# Sheet3_MCU_PSU.net
KiCad netlist of a schematic drawn in Altium Designer
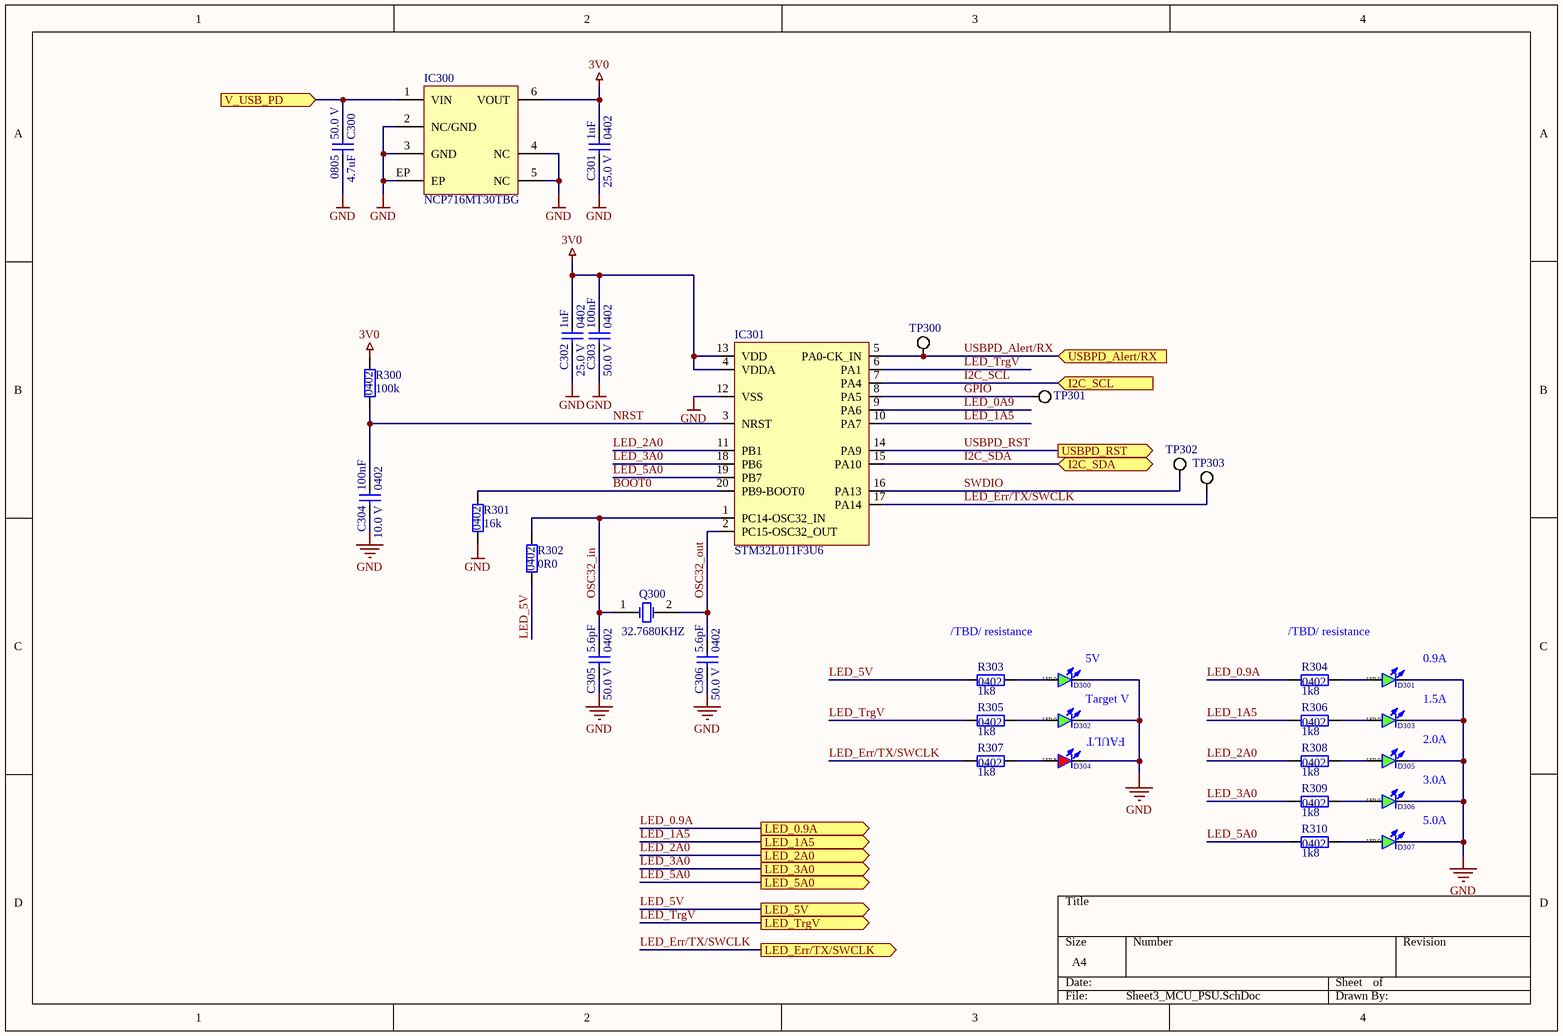
[diagram p0: Sheet3_MCU_PSU.SchDoc]

(export (version "E")
  (design (tool "Eeschema 10.0.6"))
  (components
    (comp (ref "C300")
      (value "C 4.7uF 0805 50V")
      (footprint "0805")
      (description "CAP CER 4.7UF 50V X5R 0805")
      (fields
        (field (name "MANUFACTURER") "Samsung Electro-Mechanics")
        (field (name "MANUFACTURER PART NUMBER") "CL21A475KBQNNNE")
        (field (name "CAPACITANCE") "4.7uF")
        (field (name "VOLTAGE") "50.0 V")
      )
      (libsource (lib "CS_Part_Library") (part "CAP_4.7uF_50V_0805"))
    )
    (comp (ref "C301")
      (value "C 1uF 0402 25V")
      (footprint "0402")
      (description "CAP CER 1UF 25V X5R 0402")
      (fields
        (field (name "MANUFACTURER") "Taiyo Yuden")
        (field (name "MANUFACTURER PART NUMBER") "TMK105BJ105MV-F")
        (field (name "CAPACITANCE") "1uF")
        (field (name "VOLTAGE") "25.0 V")
      )
      (libsource (lib "CS_Part_Library") (part "CAP_1uF_25V_0402"))
    )
    (comp (ref "C302")
      (value "C 1uF 0402 25V")
      (footprint "0402")
      (description "CAP CER 1UF 25V X5R 0402")
      (fields
        (field (name "MANUFACTURER") "Taiyo Yuden")
        (field (name "MANUFACTURER PART NUMBER") "TMK105BJ105MV-F")
        (field (name "CAPACITANCE") "1uF")
        (field (name "VOLTAGE") "25.0 V")
      )
      (libsource (lib "CS_Part_Library") (part "CAP_1uF_25V_0402"))
    )
    (comp (ref "C303")
      (value "C 100nF 0402 50V")
      (footprint "0402")
      (description "CAP CER 0.1UF 50V X7R 0402")
      (fields
        (field (name "MANUFACTURER") "Murata Electronics")
        (field (name "MANUFACTURER PART NUMBER") "GRM155R71H104KE14J")
        (field (name "CAPACITANCE") "100nF")
        (field (name "VOLTAGE") "50.0 V")
      )
      (libsource (lib "CS_Part_Library") (part "CAP_100nF_50V_0402"))
    )
    (comp (ref "C304")
      (value "C 100nF 0402 10V")
      (footprint "0402")
      (description "CAP CER 0.1UF 10V X5R 0402")
      (fields
        (field (name "MANUFACTURER") "Samsung Electro-Mechanics")
        (field (name "MANUFACTURER PART NUMBER") "CL05A104MP5NNNC")
        (field (name "CAPACITANCE") "100nF")
        (field (name "VOLTAGE") "10.0 V")
      )
      (libsource (lib "CS_Part_Library") (part "CAP_100nF_10V_0402"))
    )
    (comp (ref "C305")
      (value "C 5.6pF 0402 50V")
      (footprint "0402")
      (description "CAP CER 5.6PF 50V C0G/NP0 0402")
      (fields
        (field (name "MANUFACTURER") "Samsung Electro-Mechanics")
        (field (name "MANUFACTURER PART NUMBER") "CL05C5R6DB5NNNC")
        (field (name "CAPACITANCE") "5.6pF")
        (field (name "VOLTAGE") "50.0 V")
      )
      (libsource (lib "CS_Part_Library") (part "CAP_5.6PF_50V_0402"))
    )
    (comp (ref "C306")
      (value "C 5.6pF 0402 50V")
      (footprint "0402")
      (description "CAP CER 5.6PF 50V C0G/NP0 0402")
      (fields
        (field (name "MANUFACTURER") "Samsung Electro-Mechanics")
        (field (name "MANUFACTURER PART NUMBER") "CL05C5R6DB5NNNC")
        (field (name "CAPACITANCE") "5.6pF")
        (field (name "VOLTAGE") "50.0 V")
      )
      (libsource (lib "CS_Part_Library") (part "CAP_5.6PF_50V_0402"))
    )
    (comp (ref "D300")
      (value "LED G")
      (footprint "LED_0603")
      (description "LED GREEN DIFFUSED 0603 SMD")
      (fields
        (field (name "MANUFACTURER") "OSRAM Opto Semiconductors Inc.")
        (field (name "MANUFACTURER PART NUMBER") "LT Q39G-Q1OO-25-1")
      )
      (libsource (lib "CS_Part_Library") (part "D_LED_Green_0603"))
    )
    (comp (ref "D301")
      (value "LED G")
      (footprint "LED_0603")
      (description "LED GREEN DIFFUSED 0603 SMD")
      (fields
        (field (name "MANUFACTURER") "OSRAM Opto Semiconductors Inc.")
        (field (name "MANUFACTURER PART NUMBER") "LT Q39G-Q1OO-25-1")
      )
      (libsource (lib "CS_Part_Library") (part "D_LED_Green_0603"))
    )
    (comp (ref "D302")
      (value "LED G")
      (footprint "LED_0603")
      (description "LED GREEN DIFFUSED 0603 SMD")
      (fields
        (field (name "MANUFACTURER") "OSRAM Opto Semiconductors Inc.")
        (field (name "MANUFACTURER PART NUMBER") "LT Q39G-Q1OO-25-1")
      )
      (libsource (lib "CS_Part_Library") (part "D_LED_Green_0603"))
    )
    (comp (ref "D303")
      (value "LED G")
      (footprint "LED_0603")
      (description "LED GREEN DIFFUSED 0603 SMD")
      (fields
        (field (name "MANUFACTURER") "OSRAM Opto Semiconductors Inc.")
        (field (name "MANUFACTURER PART NUMBER") "LT Q39G-Q1OO-25-1")
      )
      (libsource (lib "CS_Part_Library") (part "D_LED_Green_0603"))
    )
    (comp (ref "D304")
      (value "LED R")
      (footprint "LED_0603")
      (description "LED RED DIFFUSED 0603 SMD")
      (fields
        (field (name "MANUFACTURER") "OSRAM Opto Semiconductors Inc.")
        (field (name "MANUFACTURER PART NUMBER") "LS Q976-NR-1")
      )
      (libsource (lib "CS_Part_Library") (part "D_LED_Red_0603"))
    )
    (comp (ref "D305")
      (value "LED G")
      (footprint "LED_0603")
      (description "LED GREEN DIFFUSED 0603 SMD")
      (fields
        (field (name "MANUFACTURER") "OSRAM Opto Semiconductors Inc.")
        (field (name "MANUFACTURER PART NUMBER") "LT Q39G-Q1OO-25-1")
      )
      (libsource (lib "CS_Part_Library") (part "D_LED_Green_0603"))
    )
    (comp (ref "D306")
      (value "LED G")
      (footprint "LED_0603")
      (description "LED GREEN DIFFUSED 0603 SMD")
      (fields
        (field (name "MANUFACTURER") "OSRAM Opto Semiconductors Inc.")
        (field (name "MANUFACTURER PART NUMBER") "LT Q39G-Q1OO-25-1")
      )
      (libsource (lib "CS_Part_Library") (part "D_LED_Green_0603"))
    )
    (comp (ref "D307")
      (value "LED G")
      (footprint "LED_0603")
      (description "LED GREEN DIFFUSED 0603 SMD")
      (fields
        (field (name "MANUFACTURER") "OSRAM Opto Semiconductors Inc.")
        (field (name "MANUFACTURER PART NUMBER") "LT Q39G-Q1OO-25-1")
      )
      (libsource (lib "CS_Part_Library") (part "D_LED_Green_0603"))
    )
    (comp (ref "IC300")
      (value "NCP716MT30TBG")
      (footprint "WDFN-6_EP")
      (description "IC REG LINEAR 3V 80MA 6WDFN")
      (fields (field (name "MANUFACTURER") "onsemi"))
      (libsource (lib "CS_Part_Library") (part "IC_Reg_NCP716MT30TBG"))
    )
    (comp (ref "IC301")
      (value "STM32L011F3U6")
      (footprint "UFQFN-20")
      (description "IC MCU 32BIT 8KB FLASH 20UFQFPN")
      (fields
        (field (name "MANUFACTURER") "STMicroelectronics")
        (field (name "MANUFACTURER PART NUMBER") "STM32L011F3U6TR")
      )
      (libsource (lib "CS_Part_Library") (part "IC_MCU_STM32L011F3U6"))
    )
    (comp (ref "Q300")
      (value "32.7680KHZ")
      (footprint "Q2_3.2x1.5")
      (description "CRYSTAL 32.7680KHZ 12.5PF SMD")
      (fields
        (field (name "MANUFACTURER") "NDK America, Inc.")
        (field (name "MANUFACTURER PART NUMBER") "NX3215SA-32.768K-EXS00A-MU00003")
      )
      (libsource (lib "CS_Part_Library") (part "Q_32k768_12p5"))
    )
    (comp (ref "R300")
      (value "R 100k 0402")
      (footprint "0402")
      (description "RES 100K OHM 5% 1/16W 0402")
      (fields
        (field (name "MANUFACTURER") "YAGEO")
        (field (name "MANUFACTURER PART NUMBER") "RC0402JR-07100KL")
        (field (name "RESISTANCE") "100k")
      )
      (libsource (lib "CS_Part_Library") (part "R_100k_0402"))
    )
    (comp (ref "R301")
      (value "R 16k 0402")
      (footprint "0402")
      (description "RES 16K OHM 1% 1/16W 0402")
      (fields
        (field (name "MANUFACTURER") "Stackpole Electronics Inc")
        (field (name "MANUFACTURER PART NUMBER") "RMCF0402FT16K0")
        (field (name "RESISTANCE") "16k")
      )
      (libsource (lib "CS_Part_Library") (part "R_16k_0402"))
    )
    (comp (ref "R302")
      (value "R 0R0 0402")
      (footprint "0402")
      (description "RES 0 OHM JUMPER 1/16W 0402")
      (fields
        (field (name "MANUFACTURER") "Stackpole Electronics Inc")
        (field (name "MANUFACTURER PART NUMBER") "RMCF0402ZT0R00")
        (field (name "RESISTANCE") "0R0")
      )
      (libsource (lib "CS_Part_Library") (part "R_0R0_0402"))
    )
    (comp (ref "R303")
      (value "R 1k8 0402")
      (footprint "0402")
      (description "RES 1.8K OHM 1% 1/16W 0402")
      (fields
        (field (name "MANUFACTURER") "Stackpole Electronics Inc")
        (field (name "MANUFACTURER PART NUMBER") "RMCF0402FT1K80")
        (field (name "RESISTANCE") "1k8")
      )
      (libsource (lib "CS_Part_Library") (part "R_1k8_0402"))
    )
    (comp (ref "R304")
      (value "R 1k8 0402")
      (footprint "0402")
      (description "RES 1.8K OHM 1% 1/16W 0402")
      (fields
        (field (name "MANUFACTURER") "Stackpole Electronics Inc")
        (field (name "MANUFACTURER PART NUMBER") "RMCF0402FT1K80")
        (field (name "RESISTANCE") "1k8")
      )
      (libsource (lib "CS_Part_Library") (part "R_1k8_0402"))
    )
    (comp (ref "R305")
      (value "R 1k8 0402")
      (footprint "0402")
      (description "RES 1.8K OHM 1% 1/16W 0402")
      (fields
        (field (name "MANUFACTURER") "Stackpole Electronics Inc")
        (field (name "MANUFACTURER PART NUMBER") "RMCF0402FT1K80")
        (field (name "RESISTANCE") "1k8")
      )
      (libsource (lib "CS_Part_Library") (part "R_1k8_0402"))
    )
    (comp (ref "R306")
      (value "R 1k8 0402")
      (footprint "0402")
      (description "RES 1.8K OHM 1% 1/16W 0402")
      (fields
        (field (name "MANUFACTURER") "Stackpole Electronics Inc")
        (field (name "MANUFACTURER PART NUMBER") "RMCF0402FT1K80")
        (field (name "RESISTANCE") "1k8")
      )
      (libsource (lib "CS_Part_Library") (part "R_1k8_0402"))
    )
    (comp (ref "R307")
      (value "R 1k8 0402")
      (footprint "0402")
      (description "RES 1.8K OHM 1% 1/16W 0402")
      (fields
        (field (name "MANUFACTURER") "Stackpole Electronics Inc")
        (field (name "MANUFACTURER PART NUMBER") "RMCF0402FT1K80")
        (field (name "RESISTANCE") "1k8")
      )
      (libsource (lib "CS_Part_Library") (part "R_1k8_0402"))
    )
    (comp (ref "R308")
      (value "R 1k8 0402")
      (footprint "0402")
      (description "RES 1.8K OHM 1% 1/16W 0402")
      (fields
        (field (name "MANUFACTURER") "Stackpole Electronics Inc")
        (field (name "MANUFACTURER PART NUMBER") "RMCF0402FT1K80")
        (field (name "RESISTANCE") "1k8")
      )
      (libsource (lib "CS_Part_Library") (part "R_1k8_0402"))
    )
    (comp (ref "R309")
      (value "R 1k8 0402")
      (footprint "0402")
      (description "RES 1.8K OHM 1% 1/16W 0402")
      (fields
        (field (name "MANUFACTURER") "Stackpole Electronics Inc")
        (field (name "MANUFACTURER PART NUMBER") "RMCF0402FT1K80")
        (field (name "RESISTANCE") "1k8")
      )
      (libsource (lib "CS_Part_Library") (part "R_1k8_0402"))
    )
    (comp (ref "R310")
      (value "R 1k8 0402")
      (footprint "0402")
      (description "RES 1.8K OHM 1% 1/16W 0402")
      (fields
        (field (name "MANUFACTURER") "Stackpole Electronics Inc")
        (field (name "MANUFACTURER PART NUMBER") "RMCF0402FT1K80")
        (field (name "RESISTANCE") "1k8")
      )
      (libsource (lib "CS_Part_Library") (part "R_1k8_0402"))
    )
    (comp (ref "TP300")
      (value "TP")
      (footprint "TP_1mm")
      (description "Test Point 1mm")
      (libsource (lib "CS_Part_Library") (part "TP_1mm"))
    )
    (comp (ref "TP301")
      (value "TP")
      (footprint "TP_1mm")
      (description "Test Point 1mm")
      (libsource (lib "CS_Part_Library") (part "TP_1mm"))
    )
    (comp (ref "TP302")
      (value "TP")
      (footprint "TP_1mm")
      (description "Test Point 1mm")
      (libsource (lib "CS_Part_Library") (part "TP_1mm"))
    )
    (comp (ref "TP303")
      (value "TP")
      (footprint "TP_1mm")
      (description "Test Point 1mm")
      (libsource (lib "CS_Part_Library") (part "TP_1mm"))
    )
  )
  (nets
    (net (code "1") (name "/BOOT0") (class "Default")
      (node (ref "IC301") (pin "20") (pinfunction "PB9-BOOT0_20") (pintype "passive"))
      (node (ref "R301") (pin "2") (pinfunction "2_2") (pintype "passive"))
    )
    (net (code "2") (name "/GPIO") (class "Default")
      (node (ref "IC301") (pin "8") (pinfunction "PA5_8") (pintype "passive"))
      (node (ref "TP301") (pin "1") (pinfunction "TP_1") (pintype "passive"))
    )
    (net (code "3") (name "/I2C_SCL") (class "Default")
      (node (ref "IC301") (pin "7") (pinfunction "PA4_7") (pintype "passive"))
    )
    (net (code "4") (name "/I2C_SDA") (class "Default")
      (node (ref "IC301") (pin "15") (pinfunction "PA10_15") (pintype "passive"))
    )
    (net (code "5") (name "/LED_0.9A") (class "Default")
      (node (ref "R304") (pin "2") (pinfunction "2_2") (pintype "passive"))
    )
    (net (code "6") (name "/LED_0A9") (class "Default")
      (node (ref "IC301") (pin "9") (pinfunction "PA6_9") (pintype "passive"))
    )
    (net (code "7") (name "/LED_1A5") (class "Default")
      (node (ref "IC301") (pin "10") (pinfunction "PA7_10") (pintype "passive"))
      (node (ref "R306") (pin "2") (pinfunction "2_2") (pintype "passive"))
    )
    (net (code "8") (name "/LED_2A0") (class "Default")
      (node (ref "IC301") (pin "11") (pinfunction "PB1_11") (pintype "passive"))
      (node (ref "R308") (pin "2") (pinfunction "2_2") (pintype "passive"))
    )
    (net (code "9") (name "/LED_3A0") (class "Default")
      (node (ref "IC301") (pin "18") (pinfunction "PB6_18") (pintype "passive"))
      (node (ref "R309") (pin "2") (pinfunction "2_2") (pintype "passive"))
    )
    (net (code "10") (name "/LED_5A0") (class "Default")
      (node (ref "IC301") (pin "19") (pinfunction "PB7_19") (pintype "passive"))
      (node (ref "R310") (pin "2") (pinfunction "2_2") (pintype "passive"))
    )
    (net (code "11") (name "/LED_5V") (class "Default")
      (node (ref "R302") (pin "1") (pinfunction "1_1") (pintype "passive"))
      (node (ref "R303") (pin "2") (pinfunction "2_2") (pintype "passive"))
    )
    (net (code "12") (name "/LED_Err{slash}TX{slash}SWCLK") (class "Default")
      (node (ref "IC301") (pin "17") (pinfunction "PA14_17") (pintype "passive"))
      (node (ref "R307") (pin "2") (pinfunction "2_2") (pintype "passive"))
      (node (ref "TP303") (pin "1") (pinfunction "TP_1") (pintype "passive"))
    )
    (net (code "13") (name "/LED_TrgV") (class "Default")
      (node (ref "IC301") (pin "6") (pinfunction "PA1_6") (pintype "passive"))
      (node (ref "R305") (pin "2") (pinfunction "2_2") (pintype "passive"))
    )
    (net (code "14") (name "/NRST") (class "Default")
      (node (ref "C304") (pin "2") (pinfunction "2_2") (pintype "passive"))
      (node (ref "IC301") (pin "3") (pinfunction "NRST_3") (pintype "passive"))
      (node (ref "R300") (pin "1") (pinfunction "1_1") (pintype "passive"))
    )
    (net (code "15") (name "/OSC32_in") (class "Default")
      (node (ref "C305") (pin "2") (pinfunction "2_2") (pintype "passive"))
      (node (ref "IC301") (pin "1") (pinfunction "PC14-OSC32_IN_1") (pintype "passive"))
      (node (ref "Q300") (pin "1") (pinfunction "OSC1_1") (pintype "passive"))
      (node (ref "R302") (pin "2") (pinfunction "2_2") (pintype "passive"))
    )
    (net (code "16") (name "/OSC32_out") (class "Default")
      (node (ref "C306") (pin "2") (pinfunction "2_2") (pintype "passive"))
      (node (ref "IC301") (pin "2") (pinfunction "PC15-OSC32_OUT_2") (pintype "passive"))
      (node (ref "Q300") (pin "2") (pinfunction "OSC2_2") (pintype "passive"))
    )
    (net (code "17") (name "/SWDIO") (class "Default")
      (node (ref "IC301") (pin "16") (pinfunction "PA13_16") (pintype "passive"))
      (node (ref "TP302") (pin "1") (pinfunction "TP_1") (pintype "passive"))
    )
    (net (code "18") (name "/USBPD_Alert{slash}RX") (class "Default")
      (node (ref "IC301") (pin "5") (pinfunction "PA0-CK_IN_5") (pintype "passive"))
      (node (ref "TP300") (pin "1") (pinfunction "TP_1") (pintype "passive"))
    )
    (net (code "19") (name "/USBPD_RST") (class "Default")
      (node (ref "IC301") (pin "14") (pinfunction "PA9_14") (pintype "passive"))
    )
    (net (code "20") (name "/V_USB_PD") (class "Default")
      (node (ref "C300") (pin "1") (pinfunction "1_1") (pintype "passive"))
      (node (ref "IC300") (pin "1") (pinfunction "VIN_1") (pintype "passive"))
    )
    (net (code "21") (name "3V0") (class "Default")
      (node (ref "C301") (pin "2") (pinfunction "2_2") (pintype "passive"))
      (node (ref "C302") (pin "2") (pinfunction "2_2") (pintype "passive"))
      (node (ref "C303") (pin "2") (pinfunction "2_2") (pintype "passive"))
      (node (ref "IC300") (pin "6") (pinfunction "VOUT_6") (pintype "passive"))
      (node (ref "IC301") (pin "13") (pinfunction "VDD_13") (pintype "passive"))
      (node (ref "IC301") (pin "4") (pinfunction "VDDA_4") (pintype "passive"))
      (node (ref "R300") (pin "2") (pinfunction "2_2") (pintype "passive"))
    )
    (net (code "22") (name "GND") (class "Default")
      (node (ref "C300") (pin "2") (pinfunction "2_2") (pintype "passive"))
      (node (ref "C301") (pin "1") (pinfunction "1_1") (pintype "passive"))
      (node (ref "C302") (pin "1") (pinfunction "1_1") (pintype "passive"))
      (node (ref "C303") (pin "1") (pinfunction "1_1") (pintype "passive"))
      (node (ref "C304") (pin "1") (pinfunction "1_1") (pintype "passive"))
      (node (ref "C305") (pin "1") (pinfunction "1_1") (pintype "passive"))
      (node (ref "C306") (pin "1") (pinfunction "1_1") (pintype "passive"))
      (node (ref "D300") (pin "K") (pinfunction "K_K") (pintype "passive"))
      (node (ref "D301") (pin "K") (pinfunction "K_K") (pintype "passive"))
      (node (ref "D302") (pin "K") (pinfunction "K_K") (pintype "passive"))
      (node (ref "D303") (pin "K") (pinfunction "K_K") (pintype "passive"))
      (node (ref "D304") (pin "K") (pinfunction "K_K") (pintype "passive"))
      (node (ref "D305") (pin "K") (pinfunction "K_K") (pintype "passive"))
      (node (ref "D306") (pin "K") (pinfunction "K_K") (pintype "passive"))
      (node (ref "D307") (pin "K") (pinfunction "K_K") (pintype "passive"))
      (node (ref "IC300") (pin "2") (pinfunction "NC/GND_2") (pintype "passive"))
      (node (ref "IC300") (pin "3") (pinfunction "GND_3") (pintype "passive"))
      (node (ref "IC300") (pin "4") (pinfunction "NC_4") (pintype "passive"))
      (node (ref "IC300") (pin "5") (pinfunction "NC_5") (pintype "passive"))
      (node (ref "IC300") (pin "EP") (pinfunction "EP_EP") (pintype "passive"))
      (node (ref "IC301") (pin "12") (pinfunction "VSS_12") (pintype "passive"))
      (node (ref "R301") (pin "1") (pinfunction "1_1") (pintype "passive"))
    )
    (net (code "23") (name "Net-(D300-PadA)") (class "Default")
      (node (ref "D300") (pin "A") (pinfunction "A_A") (pintype "passive"))
      (node (ref "R303") (pin "1") (pinfunction "1_1") (pintype "passive"))
    )
    (net (code "24") (name "Net-(D301-PadA)") (class "Default")
      (node (ref "D301") (pin "A") (pinfunction "A_A") (pintype "passive"))
      (node (ref "R304") (pin "1") (pinfunction "1_1") (pintype "passive"))
    )
    (net (code "25") (name "Net-(D302-PadA)") (class "Default")
      (node (ref "D302") (pin "A") (pinfunction "A_A") (pintype "passive"))
      (node (ref "R305") (pin "1") (pinfunction "1_1") (pintype "passive"))
    )
    (net (code "26") (name "Net-(D303-PadA)") (class "Default")
      (node (ref "D303") (pin "A") (pinfunction "A_A") (pintype "passive"))
      (node (ref "R306") (pin "1") (pinfunction "1_1") (pintype "passive"))
    )
    (net (code "27") (name "Net-(D304-PadA)") (class "Default")
      (node (ref "D304") (pin "A") (pinfunction "A_A") (pintype "passive"))
      (node (ref "R307") (pin "1") (pinfunction "1_1") (pintype "passive"))
    )
    (net (code "28") (name "Net-(D305-PadA)") (class "Default")
      (node (ref "D305") (pin "A") (pinfunction "A_A") (pintype "passive"))
      (node (ref "R308") (pin "1") (pinfunction "1_1") (pintype "passive"))
    )
    (net (code "29") (name "Net-(D306-PadA)") (class "Default")
      (node (ref "D306") (pin "A") (pinfunction "A_A") (pintype "passive"))
      (node (ref "R309") (pin "1") (pinfunction "1_1") (pintype "passive"))
    )
    (net (code "30") (name "Net-(D307-PadA)") (class "Default")
      (node (ref "D307") (pin "A") (pinfunction "A_A") (pintype "passive"))
      (node (ref "R310") (pin "1") (pinfunction "1_1") (pintype "passive"))
    )
  )
)
